# Main.net
KiCad netlist of a schematic drawn in Altium Designer
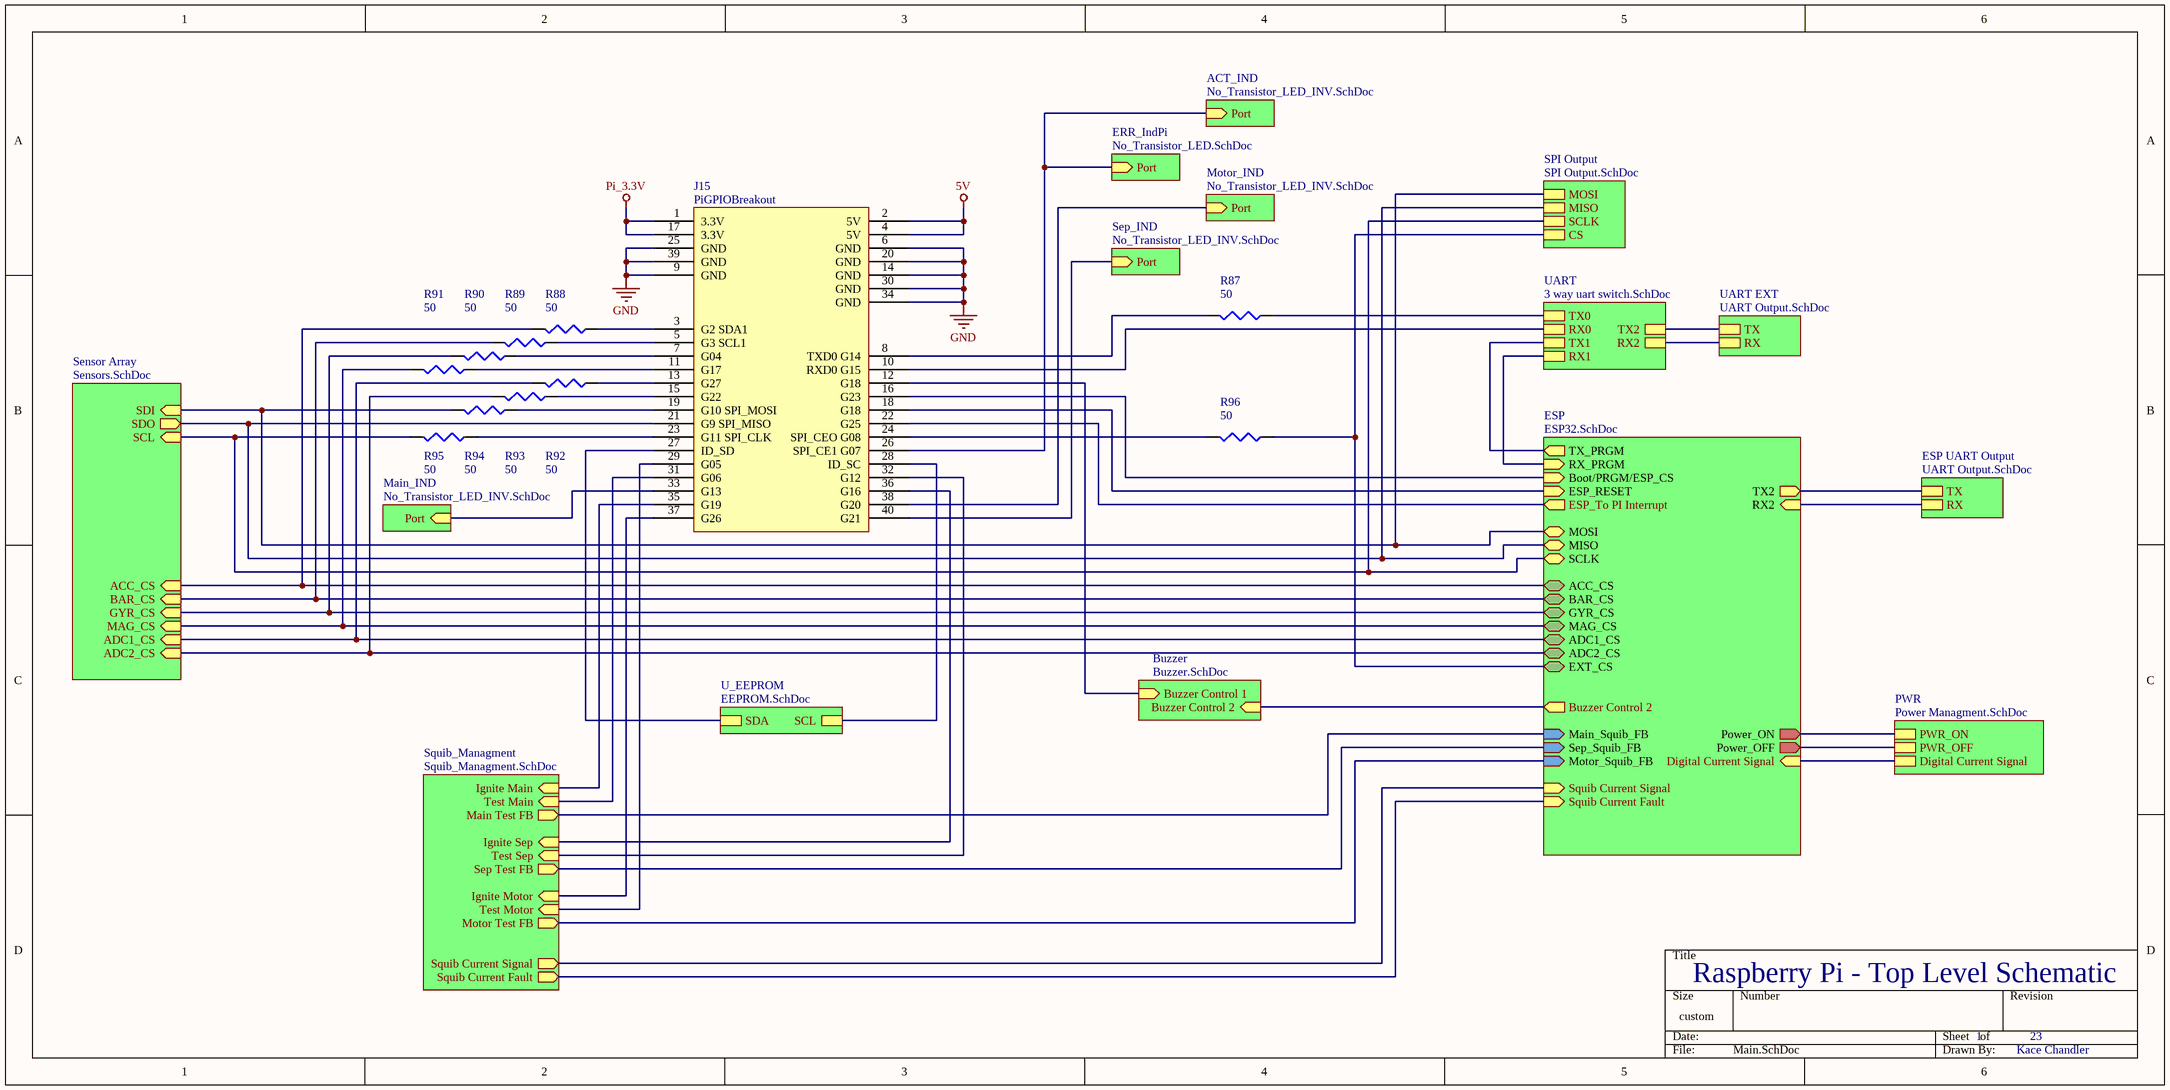
[diagram p0: Main.SchDoc]

(export (version "E")
  (design (tool "Eeschema 10.0.6"))
  (components
    (comp (ref "J15")
      (value "PiGPIOBreakout")
      (footprint "RPI Through board connector")
      (libsource (lib "AvionicsParts") (part "PiGPIOBreakout"))
    )
    (comp (ref "R87")
      (value "50")
      (description "Resistor")
      (fields (field (name "Comment") "Res3") (field (name "PUBLISHER") "Altium Limited"))
      (libsource (lib "Miscellaneous Devices") (part "Res3"))
    )
    (comp (ref "R88")
      (value "50")
      (description "Resistor")
      (fields (field (name "Comment") "Res3") (field (name "PUBLISHER") "Altium Limited"))
      (libsource (lib "Miscellaneous Devices") (part "Res3"))
    )
    (comp (ref "R89")
      (value "50")
      (description "Resistor")
      (fields (field (name "Comment") "Res3") (field (name "PUBLISHER") "Altium Limited"))
      (libsource (lib "Miscellaneous Devices") (part "Res3"))
    )
    (comp (ref "R90")
      (value "50")
      (description "Resistor")
      (fields (field (name "Comment") "Res3") (field (name "PUBLISHER") "Altium Limited"))
      (libsource (lib "Miscellaneous Devices") (part "Res3"))
    )
    (comp (ref "R91")
      (value "50")
      (description "Resistor")
      (fields (field (name "Comment") "Res3") (field (name "PUBLISHER") "Altium Limited"))
      (libsource (lib "Miscellaneous Devices") (part "Res3"))
    )
    (comp (ref "R92")
      (value "50")
      (description "Resistor")
      (fields (field (name "Comment") "Res3") (field (name "PUBLISHER") "Altium Limited"))
      (libsource (lib "Miscellaneous Devices") (part "Res3"))
    )
    (comp (ref "R93")
      (value "50")
      (description "Resistor")
      (fields (field (name "Comment") "Res3") (field (name "PUBLISHER") "Altium Limited"))
      (libsource (lib "Miscellaneous Devices") (part "Res3"))
    )
    (comp (ref "R94")
      (value "50")
      (description "Resistor")
      (fields (field (name "Comment") "Res3") (field (name "PUBLISHER") "Altium Limited"))
      (libsource (lib "Miscellaneous Devices") (part "Res3"))
    )
    (comp (ref "R95")
      (value "50")
      (description "Resistor")
      (fields (field (name "Comment") "Res3") (field (name "PUBLISHER") "Altium Limited"))
      (libsource (lib "Miscellaneous Devices") (part "Res3"))
    )
    (comp (ref "R96")
      (value "50")
      (description "Resistor")
      (fields (field (name "Comment") "Res3") (field (name "PUBLISHER") "Altium Limited"))
      (libsource (lib "Miscellaneous Devices") (part "Res3"))
    )
  )
  (nets
    (net (code "1") (name "/ACC_CS") (class "Default")
      (node (ref "R88") (pin "2") (pinfunction "2_2") (pintype "passive"))
    )
    (net (code "2") (name "/ADC1_CS") (class "Default")
      (node (ref "R92") (pin "2") (pinfunction "2_2") (pintype "passive"))
    )
    (net (code "3") (name "/ADC2_CS") (class "Default")
      (node (ref "R93") (pin "2") (pinfunction "2_2") (pintype "passive"))
    )
    (net (code "4") (name "/BAR_CS") (class "Default")
      (node (ref "R89") (pin "2") (pinfunction "2_2") (pintype "passive"))
    )
    (net (code "5") (name "/Boot{slash}PRGM{slash}ESP_CS") (class "Default")
      (node (ref "J15") (pin "16") (pinfunction "G23_16") (pintype "passive"))
    )
    (net (code "6") (name "/Buzzer Control 1") (class "Default")
      (node (ref "J15") (pin "12") (pinfunction "G18_12") (pintype "passive"))
    )
    (net (code "8") (name "/CS") (class "Default")
      (node (ref "R96") (pin "1") (pinfunction "1_1") (pintype "passive"))
    )
    (net (code "10") (name "/ESP_RESET") (class "Default")
      (node (ref "J15") (pin "18") (pinfunction "G18_18") (pintype "passive"))
    )
    (net (code "11") (name "/ESP_To PI Interrupt") (class "Default")
      (node (ref "J15") (pin "22") (pinfunction "G25_22") (pintype "passive"))
    )
    (net (code "12") (name "/GYR_CS") (class "Default")
      (node (ref "R90") (pin "2") (pinfunction "2_2") (pintype "passive"))
    )
    (net (code "13") (name "/Ignite Main") (class "Default")
      (node (ref "J15") (pin "35") (pinfunction "G19_35") (pintype "passive"))
    )
    (net (code "14") (name "/Ignite Motor") (class "Default")
      (node (ref "J15") (pin "37") (pinfunction "G26_37") (pintype "passive"))
    )
    (net (code "15") (name "/Ignite Sep") (class "Default")
      (node (ref "J15") (pin "36") (pinfunction "G16_36") (pintype "passive"))
    )
    (net (code "16") (name "/MAG_CS") (class "Default")
      (node (ref "R91") (pin "2") (pinfunction "2_2") (pintype "passive"))
    )
    (net (code "17") (name "/MOSI") (class "Default")
      (node (ref "R94") (pin "2") (pinfunction "2_2") (pintype "passive"))
    )
    (net (code "20") (name "/Port") (class "Default")
      (node (ref "J15") (pin "40") (pinfunction "G21_40") (pintype "passive"))
    )
    (net (code "21") (name "/Port_1") (class "Default")
      (node (ref "J15") (pin "33") (pinfunction "G13_33") (pintype "passive"))
    )
    (net (code "22") (name "/Port_2") (class "Default")
      (node (ref "J15") (pin "26") (pinfunction "SPI_CE1_G07_26") (pintype "passive"))
    )
    (net (code "23") (name "/Port_3") (class "Default")
      (node (ref "J15") (pin "38") (pinfunction "G20_38") (pintype "passive"))
    )
    (net (code "27") (name "/RX0") (class "Default")
      (node (ref "J15") (pin "10") (pinfunction "RXD0_G15_10") (pintype "passive"))
    )
    (net (code "30") (name "/SCL") (class "Default")
      (node (ref "J15") (pin "28") (pinfunction "ID_SC_28") (pintype "passive"))
    )
    (net (code "31") (name "/SCL_1") (class "Default")
      (node (ref "R95") (pin "2") (pinfunction "2_2") (pintype "passive"))
    )
    (net (code "32") (name "/SDA") (class "Default")
      (node (ref "J15") (pin "27") (pinfunction "ID_SD_27") (pintype "passive"))
    )
    (net (code "33") (name "/SDO") (class "Default")
      (node (ref "J15") (pin "21") (pinfunction "G9_SPI_MISO_21") (pintype "passive"))
    )
    (net (code "38") (name "/TX0") (class "Default")
      (node (ref "R87") (pin "1") (pinfunction "1_1") (pintype "passive"))
    )
    (net (code "41") (name "/Test Main") (class "Default")
      (node (ref "J15") (pin "31") (pinfunction "G06_31") (pintype "passive"))
    )
    (net (code "42") (name "/Test Motor") (class "Default")
      (node (ref "J15") (pin "29") (pinfunction "G05_29") (pintype "passive"))
    )
    (net (code "43") (name "/Test Sep") (class "Default")
      (node (ref "J15") (pin "32") (pinfunction "G12_32") (pintype "passive"))
    )
    (net (code "44") (name "5V") (class "Default")
      (node (ref "J15") (pin "2") (pinfunction "5V_2") (pintype "passive"))
      (node (ref "J15") (pin "4") (pinfunction "5V_4") (pintype "passive"))
    )
    (net (code "45") (name "GND") (class "Default")
      (node (ref "J15") (pin "14") (pinfunction "GND_14") (pintype "passive"))
      (node (ref "J15") (pin "20") (pinfunction "GND_20") (pintype "passive"))
      (node (ref "J15") (pin "25") (pinfunction "GND_25") (pintype "passive"))
      (node (ref "J15") (pin "30") (pinfunction "GND_30") (pintype "passive"))
      (node (ref "J15") (pin "34") (pinfunction "GND_34") (pintype "passive"))
      (node (ref "J15") (pin "39") (pinfunction "GND_39") (pintype "passive"))
      (node (ref "J15") (pin "6") (pinfunction "GND_6") (pintype "passive"))
      (node (ref "J15") (pin "9") (pinfunction "GND_9") (pintype "passive"))
    )
    (net (code "46") (name "Net-(J15-G2_SDA1)") (class "Default")
      (node (ref "J15") (pin "3") (pinfunction "G2_SDA1_3") (pintype "passive"))
      (node (ref "R88") (pin "1") (pinfunction "1_1") (pintype "passive"))
    )
    (net (code "47") (name "Net-(J15-G3_SCL1)") (class "Default")
      (node (ref "J15") (pin "5") (pinfunction "G3_SCL1_5") (pintype "passive"))
      (node (ref "R89") (pin "1") (pinfunction "1_1") (pintype "passive"))
    )
    (net (code "48") (name "Net-(J15-G04)") (class "Default")
      (node (ref "J15") (pin "7") (pinfunction "G04_7") (pintype "passive"))
      (node (ref "R90") (pin "1") (pinfunction "1_1") (pintype "passive"))
    )
    (net (code "49") (name "Net-(J15-G10_SPI_MOSI)") (class "Default")
      (node (ref "J15") (pin "19") (pinfunction "G10_SPI_MOSI_19") (pintype "passive"))
      (node (ref "R94") (pin "1") (pinfunction "1_1") (pintype "passive"))
    )
    (net (code "50") (name "Net-(J15-G11_SPI_CLK)") (class "Default")
      (node (ref "J15") (pin "23") (pinfunction "G11_SPI_CLK_23") (pintype "passive"))
      (node (ref "R95") (pin "1") (pinfunction "1_1") (pintype "passive"))
    )
    (net (code "51") (name "Net-(J15-G17)") (class "Default")
      (node (ref "J15") (pin "11") (pinfunction "G17_11") (pintype "passive"))
      (node (ref "R91") (pin "1") (pinfunction "1_1") (pintype "passive"))
    )
    (net (code "52") (name "Net-(J15-G22)") (class "Default")
      (node (ref "J15") (pin "15") (pinfunction "G22_15") (pintype "passive"))
      (node (ref "R93") (pin "1") (pinfunction "1_1") (pintype "passive"))
    )
    (net (code "53") (name "Net-(J15-G27)") (class "Default")
      (node (ref "J15") (pin "13") (pinfunction "G27_13") (pintype "passive"))
      (node (ref "R92") (pin "1") (pinfunction "1_1") (pintype "passive"))
    )
    (net (code "54") (name "Net-(J15-SPI_CEO_G08)") (class "Default")
      (node (ref "J15") (pin "24") (pinfunction "SPI_CEO_G08_24") (pintype "passive"))
      (node (ref "R96") (pin "2") (pinfunction "2_2") (pintype "passive"))
    )
    (net (code "55") (name "Net-(J15-TXD0_G14)") (class "Default")
      (node (ref "J15") (pin "8") (pinfunction "TXD0_G14_8") (pintype "passive"))
      (node (ref "R87") (pin "2") (pinfunction "2_2") (pintype "passive"))
    )
    (net (code "56") (name "Pi_3.3V") (class "Default")
      (node (ref "J15") (pin "1") (pinfunction "3.3V_1") (pintype "passive"))
      (node (ref "J15") (pin "17") (pinfunction "3.3V_17") (pintype "passive"))
    )
  )
)
